# 51-2001-01-9_04_Power_Module_Schematic.net
KiCad netlist of a schematic drawn in Altium Designer
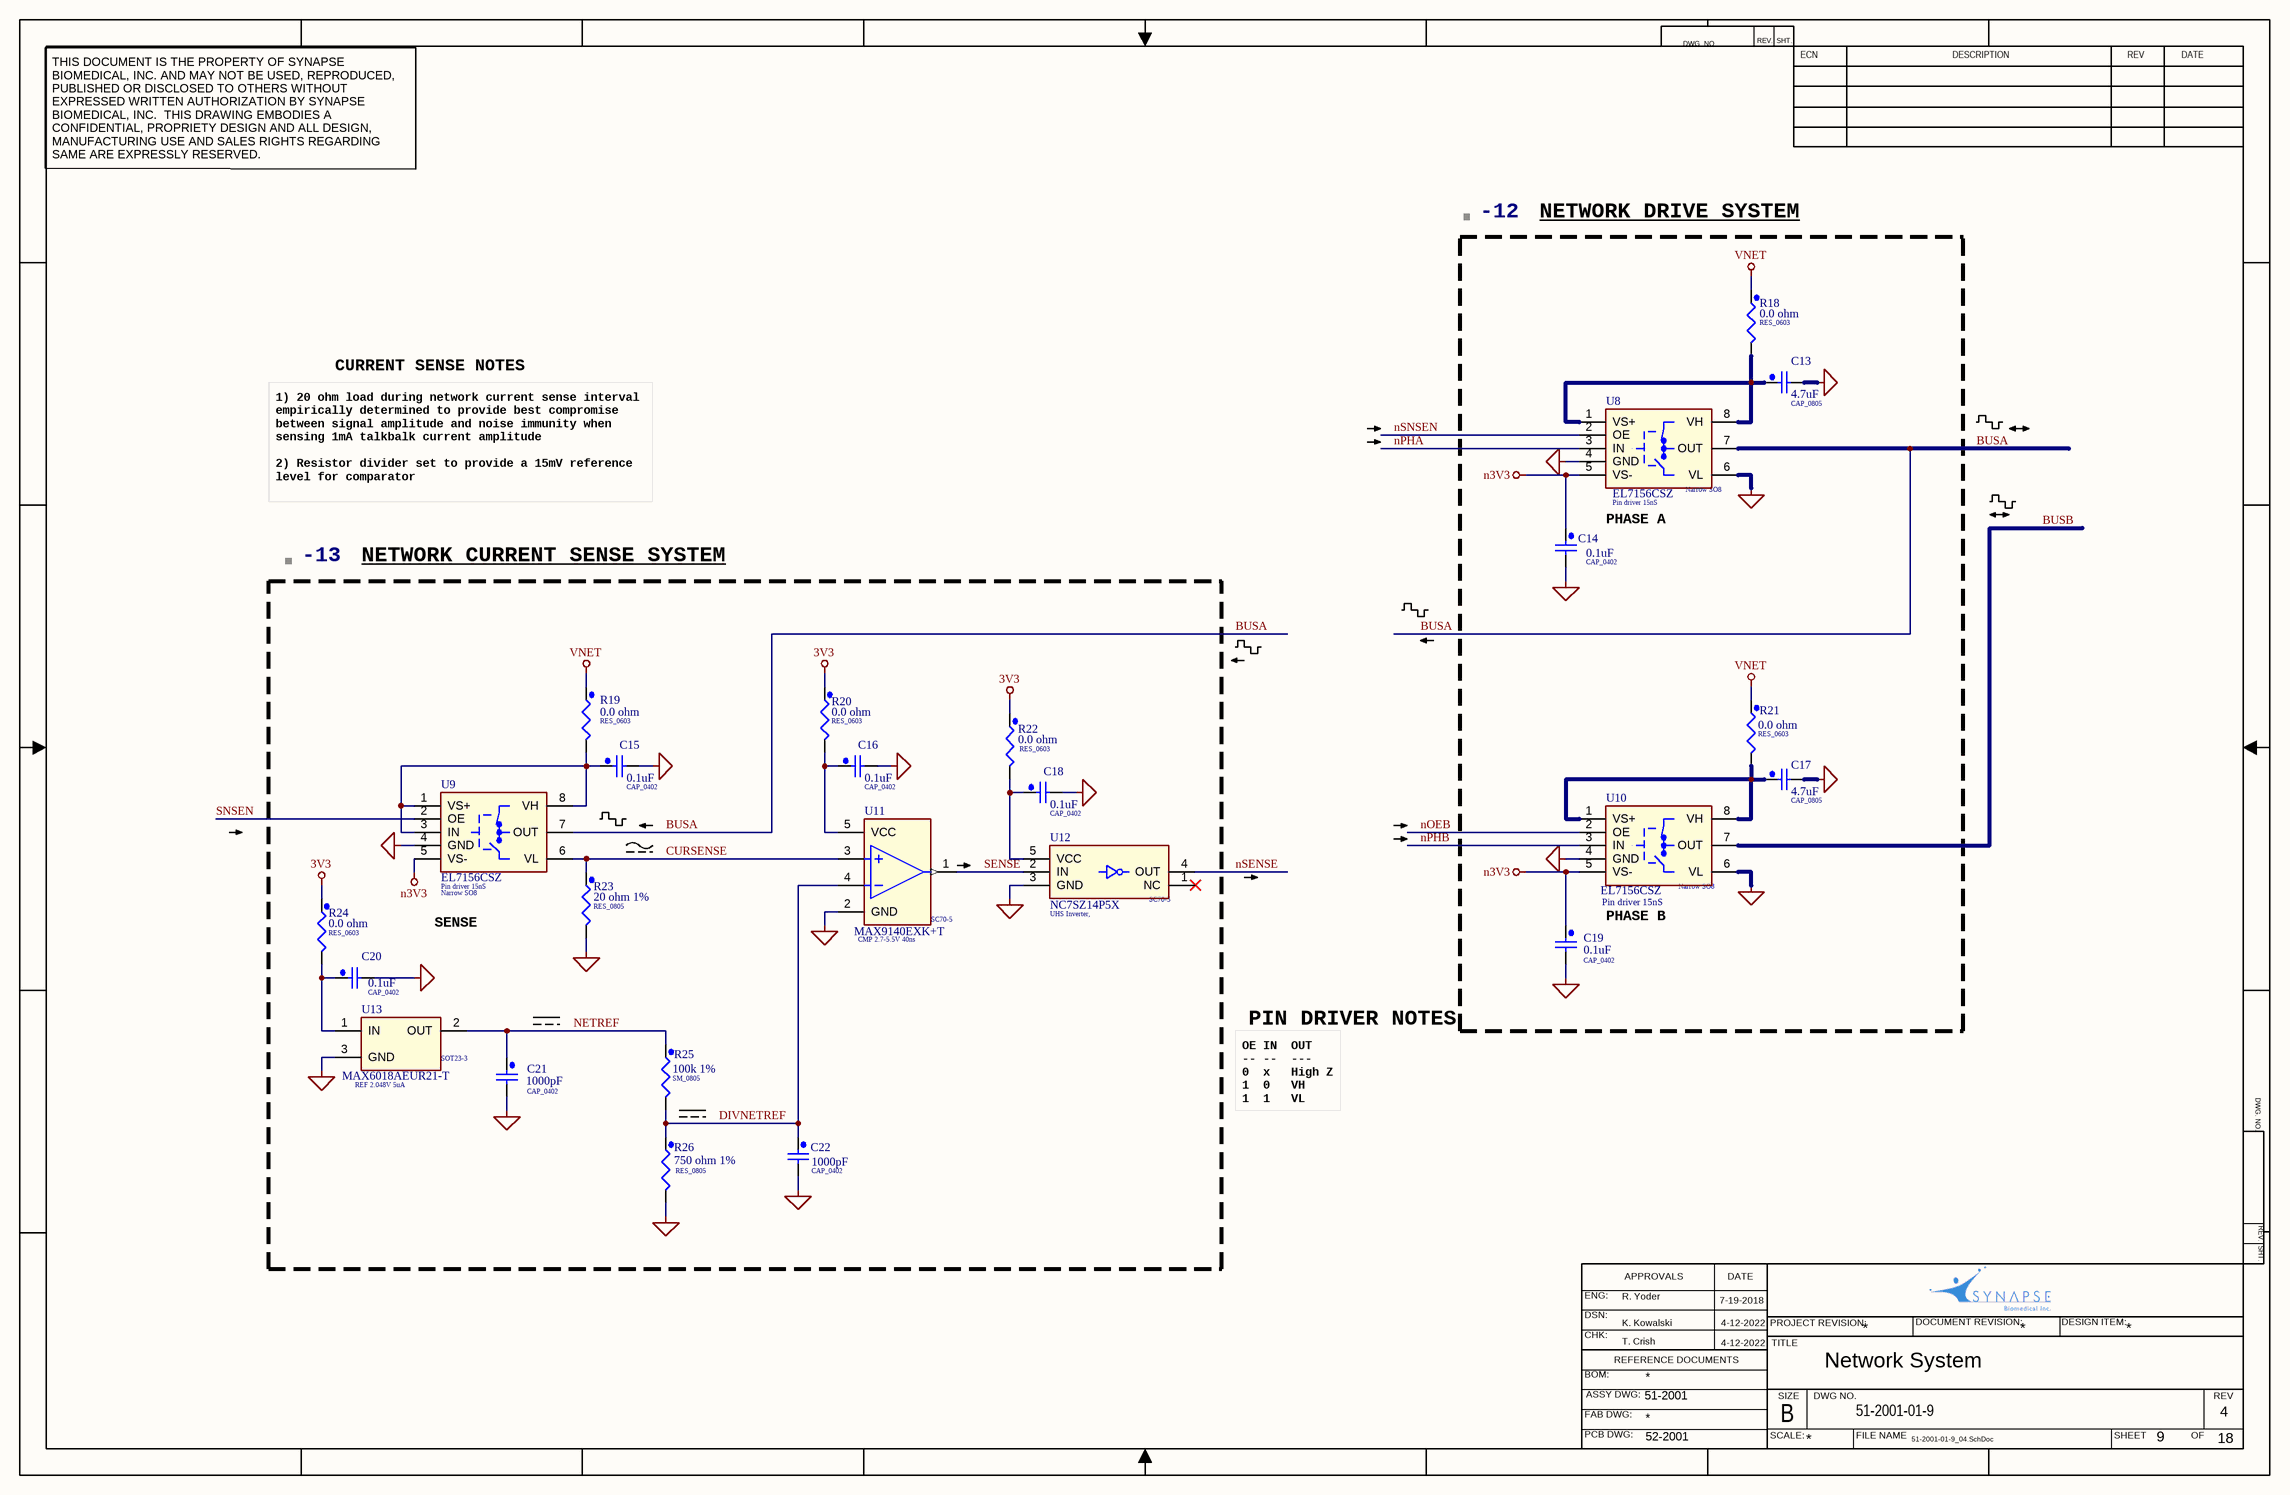
[diagram p0: 51-2001-01-9_04 Power Module Schematic.SchDoc]

(export (version "E")
  (design (tool "Eeschema 10.0.6"))
  (components
    (comp (ref "-12")
      (value "BOM_S1")
      (description "BOM item small graphic")
      (fields (field (name "XDESCRIPTION") "NETWORK DRIVE SYSTEM"))
      (libsource (lib "BOM_sym") (part "BOM_S1"))
    )
    (comp (ref "-13")
      (value "BOM_S1")
      (description "BOM item small graphic")
      (fields (field (name "XDESCRIPTION") "NETWORK CURRENT SENSE SYSTEM"))
      (libsource (lib "BOM_sym") (part "BOM_S1"))
    )
    (comp (ref "C13")
      (value "4.7uF")
      (footprint "CAP_0805")
      (description "4.7uF, 25V, X5R, 10%, 0805, RoHS")
      (fields
        (field (name "MFR") "Murata Electronics North America")
        (field (name "PACKAGEDESCRIPTION") "CAP_0805")
        (field (name "MPN") "GRM21BR61E475KA12L")
      )
      (libsource (lib "NNPS Integrated Parts") (part "TMK212BJ475KG-T"))
    )
    (comp (ref "C14")
      (value "0.1uF")
      (footprint "CAP_0402")
      (description "0.1uF, 16V, X7R, 0402, RoHS")
      (fields
        (field (name "MFR") "Murata")
        (field (name "PACKAGEDESCRIPTION") "CAP_0402")
        (field (name "MPN") "GRM155R71C104KA88D")
      )
      (libsource (lib "NNPS Integrated Parts") (part "GRM155R71C104KA88D"))
    )
    (comp (ref "C15")
      (value "0.1uF")
      (footprint "CAP_0402")
      (description "0.1uF, 16V, X7R, 0402, RoHS")
      (fields
        (field (name "MFR") "Murata")
        (field (name "PACKAGEDESCRIPTION") "CAP_0402")
        (field (name "MPN") "GRM155R71C104KA88D")
      )
      (libsource (lib "NNPS Integrated Parts") (part "GRM155R71C104KA88D"))
    )
    (comp (ref "C16")
      (value "0.1uF")
      (footprint "CAP_0402")
      (description "0.1uF, 16V, X7R, 0402, RoHS")
      (fields
        (field (name "MFR") "Murata")
        (field (name "PACKAGEDESCRIPTION") "CAP_0402")
        (field (name "MPN") "GRM155R71C104KA88D")
      )
      (libsource (lib "NNPS Integrated Parts") (part "GRM155R71C104KA88D"))
    )
    (comp (ref "C17")
      (value "4.7uF")
      (footprint "CAP_0805")
      (description "4.7uF, 25V, X5R, 10%, 0805, RoHS")
      (fields
        (field (name "MFR") "Murata Electronics North America")
        (field (name "PACKAGEDESCRIPTION") "CAP_0805")
        (field (name "MPN") "GRM21BR61E475KA12L")
      )
      (libsource (lib "NNPS Integrated Parts") (part "TMK212BJ475KG-T"))
    )
    (comp (ref "C18")
      (value "0.1uF")
      (footprint "CAP_0402")
      (description "0.1uF, 16V, X7R, 0402, RoHS")
      (fields
        (field (name "MFR") "Murata")
        (field (name "PACKAGEDESCRIPTION") "CAP_0402")
        (field (name "MPN") "GRM155R71C104KA88D")
      )
      (libsource (lib "NNPS Integrated Parts") (part "GRM155R71C104KA88D"))
    )
    (comp (ref "C19")
      (value "0.1uF")
      (footprint "CAP_0402")
      (description "0.1uF, 16V, X7R, 0402, RoHS")
      (fields
        (field (name "MFR") "Murata")
        (field (name "PACKAGEDESCRIPTION") "CAP_0402")
        (field (name "MPN") "GRM155R71C104KA88D")
      )
      (libsource (lib "NNPS Integrated Parts") (part "GRM155R71C104KA88D"))
    )
    (comp (ref "C20")
      (value "0.1uF")
      (footprint "CAP_0402")
      (description "0.1uF, 16V, X7R, 0402, RoHS")
      (fields
        (field (name "MFR") "Murata")
        (field (name "PACKAGEDESCRIPTION") "CAP_0402")
        (field (name "MPN") "GRM155R71C104KA88D")
      )
      (libsource (lib "NNPS Integrated Parts") (part "GRM155R71C104KA88D"))
    )
    (comp (ref "C21")
      (value "1000pF")
      (footprint "CAP_0402")
      (description "1000pF, 50V, C0G, 5%, 0402, RoHS")
      (fields
        (field (name "MFR") "Murata")
        (field (name "PACKAGEDESCRIPTION") "CAP_0402")
        (field (name "MPN") "GRM1555C1H102JA01D")
      )
      (libsource (lib "NNPS Integrated Parts") (part "GRM1555C1H102JA01D"))
    )
    (comp (ref "C22")
      (value "1000pF")
      (footprint "CAP_0402")
      (description "1000pF, 50V, C0G, 5%, 0402, RoHS")
      (fields
        (field (name "MFR") "Murata")
        (field (name "PACKAGEDESCRIPTION") "CAP_0402")
        (field (name "MPN") "GRM1555C1H102JA01D")
      )
      (libsource (lib "NNPS Integrated Parts") (part "GRM1555C1H102JA01D"))
    )
    (comp (ref "R18")
      (value "0.0 ohm")
      (footprint "RES_0603")
      (description "0.0 ohm, 1/16W, 0603, RoHS")
      (fields
        (field (name "MFR") "Vishay Dale")
        (field (name "PACKAGEDESCRIPTION") "RES_0603")
        (field (name "MPN") "CRCW06030000Z0EA")
      )
      (libsource (lib "NNPS Integrated Parts") (part "MCR03ERTJ000"))
    )
    (comp (ref "R19")
      (value "0.0 ohm")
      (footprint "RES_0603")
      (description "0.0 ohm, 1/16W, 0603, RoHS")
      (fields
        (field (name "MFR") "Vishay Dale")
        (field (name "PACKAGEDESCRIPTION") "RES_0603")
        (field (name "MPN") "CRCW06030000Z0EA")
      )
      (libsource (lib "NNPS Integrated Parts") (part "MCR03ERTJ000"))
    )
    (comp (ref "R20")
      (value "0.0 ohm")
      (footprint "RES_0603")
      (description "0.0 ohm, 1/16W, 0603, RoHS")
      (fields
        (field (name "MFR") "Vishay Dale")
        (field (name "PACKAGEDESCRIPTION") "RES_0603")
        (field (name "MPN") "CRCW06030000Z0EA")
      )
      (libsource (lib "NNPS Integrated Parts") (part "MCR03ERTJ000"))
    )
    (comp (ref "R21")
      (value "0.0 ohm")
      (footprint "RES_0603")
      (description "0.0 ohm, 1/16W, 0603, RoHS")
      (fields
        (field (name "MFR") "Vishay Dale")
        (field (name "PACKAGEDESCRIPTION") "RES_0603")
        (field (name "MPN") "CRCW06030000Z0EA")
      )
      (libsource (lib "NNPS Integrated Parts") (part "MCR03ERTJ000"))
    )
    (comp (ref "R22")
      (value "0.0 ohm")
      (footprint "RES_0603")
      (description "0.0 ohm, 1/16W, 0603, RoHS")
      (fields
        (field (name "MFR") "Vishay Dale")
        (field (name "PACKAGEDESCRIPTION") "RES_0603")
        (field (name "MPN") "CRCW06030000Z0EA")
      )
      (libsource (lib "NNPS Integrated Parts") (part "MCR03ERTJ000"))
    )
    (comp (ref "R23")
      (value "20 ohm 1%")
      (footprint "RES_0805")
      (description "20 ohm, 1%, 1/8W, 0805, RoHS")
      (fields
        (field (name "MFR") "Vishay Dale")
        (field (name "PACKAGEDESCRIPTION") "RES_0805")
        (field (name "MPN") "CRCW080520R0FKEA")
      )
      (libsource (lib "NNPS Integrated Parts") (part "MCR10EZHF20R0"))
    )
    (comp (ref "R24")
      (value "0.0 ohm")
      (footprint "RES_0603")
      (description "0.0 ohm, 1/16W, 0603, RoHS")
      (fields
        (field (name "MFR") "Vishay Dale")
        (field (name "PACKAGEDESCRIPTION") "RES_0603")
        (field (name "MPN") "CRCW06030000Z0EA")
      )
      (libsource (lib "NNPS Integrated Parts") (part "MCR03ERTJ000"))
    )
    (comp (ref "R25")
      (value "100k 1%")
      (footprint "RES_0805")
      (description "100k ohm, 0.1%, 1/8W, 0805, RoHS")
      (fields
        (field (name "MFR") "Vishay Dale")
        (field (name "PACKAGEDESCRIPTION") "SM_0805")
        (field (name "MPN") "TNPW0805100KBEEA")
      )
      (libsource (lib "NNPS Integrated Parts") (part "RG2012P-104-B-T5"))
    )
    (comp (ref "R26")
      (value "750 ohm 1%")
      (footprint "RES_0805")
      (description "750 ohm, 0.1%, 1/8W, 080, RoHS")
      (fields
        (field (name "MFR") "Susumu")
        (field (name "PACKAGEDESCRIPTION") "RES_0805")
        (field (name "MPN") "RG2012P-751-B-T5")
      )
      (libsource (lib "NNPS Integrated Parts") (part "RG2012P-751-B-T5"))
    )
    (comp (ref "U8")
      (value "Pin driver 15nS")
      (footprint "SOIC8-N")
      (description "Pin driver, 15nS,  40 MHz, SO8, RoHS")
      (fields
        (field (name "MFR") "Intersil")
        (field (name "PACKAGEDESCRIPTION") "Narrow SO8")
        (field (name "MPN") "EL7156CSZ")
      )
      (libsource (lib "NNPS Integrated Parts") (part "EL7156CSZ"))
    )
    (comp (ref "U9")
      (value "Pin driver 15nS")
      (footprint "SOIC8-N")
      (description "Pin driver, 15nS,  40 MHz, SO8, RoHS")
      (fields
        (field (name "MFR") "Intersil")
        (field (name "PACKAGEDESCRIPTION") "Narrow SO8")
        (field (name "MPN") "EL7156CSZ")
      )
      (libsource (lib "NNPS Integrated Parts") (part "EL7156CSZ"))
    )
    (comp (ref "U10")
      (value "Pin driver 15nS")
      (footprint "SOIC8-N")
      (description "Pin driver, 15nS,  40 MHz, SO8, RoHS")
      (fields
        (field (name "MFR") "Intersil")
        (field (name "PACKAGEDESCRIPTION") "Narrow SO8")
        (field (name "MPN") "EL7156CSZ")
      )
      (libsource (lib "NNPS Integrated Parts") (part "EL7156CSZ"))
    )
    (comp (ref "U11")
      (value "CMP 2.7-5.5V 40ns")
      (footprint "SC70-5")
      (description "Comparator, 2.7-5.5V, 40ns, SC70-5, RoHS")
      (fields
        (field (name "PACKAGEDESCRIPTION") "SC70-5")
        (field (name "MFR") "Maxim Integrated")
        (field (name "MPN") "MAX9140EXK+T")
      )
      (libsource (lib "NNPS Integrated Parts") (part "MAX9140EXK"))
    )
    (comp (ref "U12")
      (value "UHS Inverter,")
      (footprint "SC70-5")
      (description "Ultra high speed Inverter, SC70-5, RoHS")
      (fields
        (field (name "MFR") "Fairchild")
        (field (name "PACKAGEDESCRIPTION") "SC70-5")
        (field (name "MPN") "NC7SZ14P5X")
      )
      (libsource (lib "NNPS Integrated Parts") (part "NC7SZ14P5X"))
    )
    (comp (ref "U13")
      (value "REF 2.048V 5uA")
      (footprint "SOT23-3")
      (description "Ref, 2.048V, 5uA, SOT23-3, RoHS")
      (fields
        (field (name "PACKAGEDESCRIPTION") "SOT23-3")
        (field (name "MFR") "Maxim Integrated")
        (field (name "MPN") "MAX6018AEUR21-T")
      )
      (libsource (lib "NNPS Integrated Parts") (part "MAX6018AEUR21-T"))
    )
  )
  (nets
    (net (code "1") (name "/BUSA") (class "Default")
      (node (ref "U8") (pin "7") (pinfunction "OUT_7") (pintype "passive"))
      (node (ref "U9") (pin "7") (pinfunction "OUT_7") (pintype "passive"))
    )
    (net (code "2") (name "/BUSB") (class "Default")
      (node (ref "U10") (pin "7") (pinfunction "OUT_7") (pintype "passive"))
    )
    (net (code "3") (name "/CURSENSE") (class "Default")
      (node (ref "R23") (pin "1") (pinfunction "1_1") (pintype "passive"))
      (node (ref "U11") (pin "3") (pinfunction "IN+_3") (pintype "tri_state"))
      (node (ref "U9") (pin "6") (pinfunction "VL_6") (pintype "passive"))
    )
    (net (code "4") (name "/DIVNETREF") (class "Default")
      (node (ref "C22") (pin "1") (pinfunction "1_1") (pintype "passive"))
      (node (ref "R25") (pin "2") (pinfunction "2_2") (pintype "passive"))
      (node (ref "R26") (pin "1") (pinfunction "1_1") (pintype "passive"))
      (node (ref "U11") (pin "4") (pinfunction "IN-_4") (pintype "tri_state"))
    )
    (net (code "5") (name "/NETREF") (class "Default")
      (node (ref "C21") (pin "1") (pinfunction "1_1") (pintype "passive"))
      (node (ref "R25") (pin "1") (pinfunction "1_1") (pintype "passive"))
      (node (ref "U13") (pin "2") (pinfunction "OUT_2") (pintype "passive"))
    )
    (net (code "6") (name "/SENSE") (class "Default")
      (node (ref "U11") (pin "1") (pinfunction "OUTA_1") (pintype "output"))
      (node (ref "U12") (pin "2") (pinfunction "IN_2") (pintype "passive"))
    )
    (net (code "7") (name "/SNSEN") (class "Default")
      (node (ref "U9") (pin "2") (pinfunction "OE_2") (pintype "passive"))
    )
    (net (code "8") (name "/nOEB") (class "Default")
      (node (ref "U10") (pin "2") (pinfunction "OE_2") (pintype "passive"))
    )
    (net (code "9") (name "/nPHA") (class "Default")
      (node (ref "U8") (pin "3") (pinfunction "IN_3") (pintype "passive"))
    )
    (net (code "10") (name "/nPHB") (class "Default")
      (node (ref "U10") (pin "3") (pinfunction "IN_3") (pintype "passive"))
    )
    (net (code "11") (name "/nSENSE") (class "Default")
      (node (ref "U12") (pin "4") (pinfunction "OUT_4") (pintype "passive"))
    )
    (net (code "12") (name "/nSNSEN") (class "Default")
      (node (ref "U8") (pin "2") (pinfunction "OE_2") (pintype "passive"))
    )
    (net (code "13") (name "3V3") (class "Default")
      (node (ref "R20") (pin "1") (pinfunction "1_1") (pintype "passive"))
      (node (ref "R22") (pin "1") (pinfunction "1_1") (pintype "passive"))
      (node (ref "R24") (pin "1") (pinfunction "1_1") (pintype "passive"))
    )
    (net (code "14") (name "GND") (class "Default")
      (node (ref "C13") (pin "2") (pinfunction "2_2") (pintype "passive"))
      (node (ref "C14") (pin "2") (pinfunction "2_2") (pintype "passive"))
      (node (ref "C15") (pin "2") (pinfunction "2_2") (pintype "passive"))
      (node (ref "C16") (pin "2") (pinfunction "2_2") (pintype "passive"))
      (node (ref "C17") (pin "2") (pinfunction "2_2") (pintype "passive"))
      (node (ref "C18") (pin "2") (pinfunction "2_2") (pintype "passive"))
      (node (ref "C19") (pin "2") (pinfunction "2_2") (pintype "passive"))
      (node (ref "C20") (pin "2") (pinfunction "2_2") (pintype "passive"))
      (node (ref "C21") (pin "2") (pinfunction "2_2") (pintype "passive"))
      (node (ref "C22") (pin "2") (pinfunction "2_2") (pintype "passive"))
      (node (ref "R23") (pin "2") (pinfunction "2_2") (pintype "passive"))
      (node (ref "R26") (pin "2") (pinfunction "2_2") (pintype "passive"))
      (node (ref "U10") (pin "4") (pinfunction "GND_4") (pintype "passive"))
      (node (ref "U10") (pin "6") (pinfunction "VL_6") (pintype "passive"))
      (node (ref "U11") (pin "2") (pinfunction "GND_2") (pintype "power_in"))
      (node (ref "U12") (pin "3") (pinfunction "GND_3") (pintype "passive"))
      (node (ref "U13") (pin "3") (pinfunction "GND_3") (pintype "passive"))
      (node (ref "U8") (pin "4") (pinfunction "GND_4") (pintype "passive"))
      (node (ref "U8") (pin "6") (pinfunction "VL_6") (pintype "passive"))
      (node (ref "U9") (pin "4") (pinfunction "GND_4") (pintype "passive"))
    )
    (net (code "15") (name "Net-(U8-VH)") (class "Default")
      (node (ref "C13") (pin "1") (pinfunction "1_1") (pintype "passive"))
      (node (ref "R18") (pin "2") (pinfunction "2_2") (pintype "passive"))
      (node (ref "U8") (pin "1") (pinfunction "VS+_1") (pintype "passive"))
      (node (ref "U8") (pin "8") (pinfunction "VH_8") (pintype "passive"))
    )
    (net (code "16") (name "Net-(U9-IN)") (class "Default")
      (node (ref "C15") (pin "1") (pinfunction "1_1") (pintype "passive"))
      (node (ref "R19") (pin "2") (pinfunction "2_2") (pintype "passive"))
      (node (ref "U9") (pin "1") (pinfunction "VS+_1") (pintype "passive"))
      (node (ref "U9") (pin "3") (pinfunction "IN_3") (pintype "passive"))
      (node (ref "U9") (pin "8") (pinfunction "VH_8") (pintype "passive"))
    )
    (net (code "17") (name "Net-(U10-VH)") (class "Default")
      (node (ref "C17") (pin "1") (pinfunction "1_1") (pintype "passive"))
      (node (ref "R21") (pin "2") (pinfunction "2_2") (pintype "passive"))
      (node (ref "U10") (pin "1") (pinfunction "VS+_1") (pintype "passive"))
      (node (ref "U10") (pin "8") (pinfunction "VH_8") (pintype "passive"))
    )
    (net (code "18") (name "Net-(U11-VCC)") (class "Default")
      (node (ref "C16") (pin "1") (pinfunction "1_1") (pintype "passive"))
      (node (ref "R20") (pin "2") (pinfunction "2_2") (pintype "passive"))
      (node (ref "U11") (pin "5") (pinfunction "VCC_5") (pintype "power_in"))
    )
    (net (code "19") (name "Net-(U12-VCC)") (class "Default")
      (node (ref "C18") (pin "1") (pinfunction "1_1") (pintype "passive"))
      (node (ref "R22") (pin "2") (pinfunction "2_2") (pintype "passive"))
      (node (ref "U12") (pin "5") (pinfunction "VCC_5") (pintype "passive"))
    )
    (net (code "20") (name "Net-(U13-IN)") (class "Default")
      (node (ref "C20") (pin "1") (pinfunction "1_1") (pintype "passive"))
      (node (ref "R24") (pin "2") (pinfunction "2_2") (pintype "passive"))
      (node (ref "U13") (pin "1") (pinfunction "IN_1") (pintype "passive"))
    )
    (net (code "21") (name "VNET") (class "Default")
      (node (ref "R18") (pin "1") (pinfunction "1_1") (pintype "passive"))
      (node (ref "R19") (pin "1") (pinfunction "1_1") (pintype "passive"))
      (node (ref "R21") (pin "1") (pinfunction "1_1") (pintype "passive"))
    )
    (net (code "22") (name "n3V3") (class "Default")
      (node (ref "C14") (pin "1") (pinfunction "1_1") (pintype "passive"))
      (node (ref "C19") (pin "1") (pinfunction "1_1") (pintype "passive"))
      (node (ref "U10") (pin "5") (pinfunction "VS-_5") (pintype "passive"))
      (node (ref "U8") (pin "5") (pinfunction "VS-_5") (pintype "passive"))
      (node (ref "U9") (pin "5") (pinfunction "VS-_5") (pintype "passive"))
    )
    (net (code "23") (name "unconnected-(U12-NC-Pad1)") (class "Default")
      (node (ref "U12") (pin "1") (pinfunction "NC_1") (pintype "passive+no_connect"))
    )
  )
)
